# JetBot_Verteiler.net
KiCad netlist of a schematic drawn in EAGLE
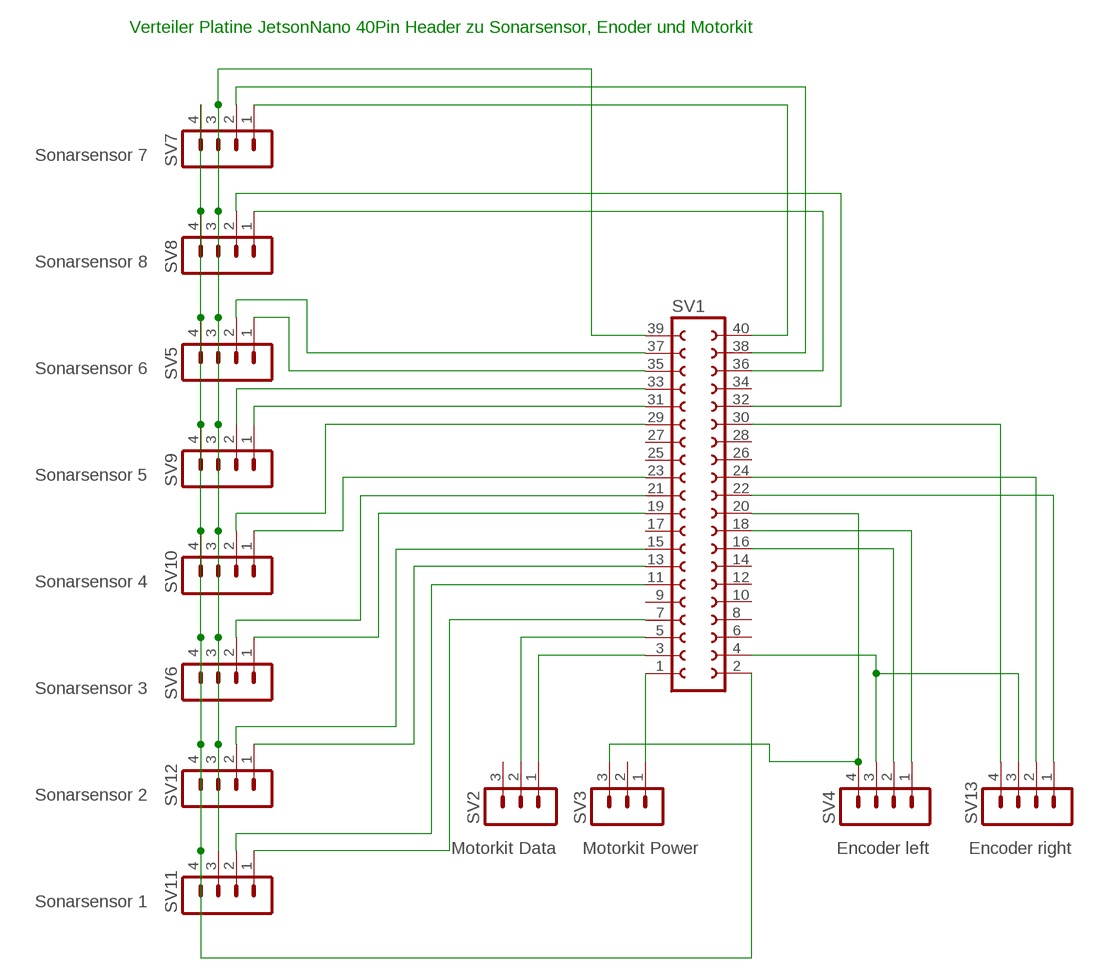
[diagram p0: schematic, sheet 1]

(export (version "E")
  (design (tool "Eeschema 10.0.6"))
  (components
    (comp (ref "SV1")
      (value "FE20-2")
      (footprint "eagle-import:FE20-2")
      (libsource (lib "eagle-import") (part "FE20-2"))
    )
    (comp (ref "SV2")
      (value "Motorkit Data")
      (footprint "eagle-import:MA03-1")
      (libsource (lib "eagle-import") (part "MA03-1"))
    )
    (comp (ref "SV3")
      (value "Motorkit Power")
      (footprint "eagle-import:MA03-1")
      (libsource (lib "eagle-import") (part "MA03-1"))
    )
    (comp (ref "SV4")
      (value "Encoder left")
      (footprint "eagle-import:MA04-1")
      (libsource (lib "eagle-import") (part "MA04-1"))
    )
    (comp (ref "SV5")
      (value "Sonarsensor 6")
      (footprint "eagle-import:MA04-1")
      (libsource (lib "eagle-import") (part "MA04-1"))
    )
    (comp (ref "SV6")
      (value "Sonarsensor 3")
      (footprint "eagle-import:MA04-1")
      (libsource (lib "eagle-import") (part "MA04-1"))
    )
    (comp (ref "SV7")
      (value "Sonarsensor 7")
      (footprint "eagle-import:MA04-1")
      (libsource (lib "eagle-import") (part "MA04-1"))
    )
    (comp (ref "SV8")
      (value "Sonarsensor 8")
      (footprint "eagle-import:MA04-1")
      (libsource (lib "eagle-import") (part "MA04-1"))
    )
    (comp (ref "SV9")
      (value "Sonarsensor 5")
      (footprint "eagle-import:MA04-1")
      (libsource (lib "eagle-import") (part "MA04-1"))
    )
    (comp (ref "SV10")
      (value "Sonarsensor 4")
      (footprint "eagle-import:MA04-1")
      (libsource (lib "eagle-import") (part "MA04-1"))
    )
    (comp (ref "SV11")
      (value "Sonarsensor 1")
      (footprint "eagle-import:MA04-1")
      (libsource (lib "eagle-import") (part "MA04-1"))
    )
    (comp (ref "SV12")
      (value "Sonarsensor 2")
      (footprint "eagle-import:MA04-1")
      (libsource (lib "eagle-import") (part "MA04-1"))
    )
    (comp (ref "SV13")
      (value "Encoder right")
      (footprint "eagle-import:MA04-1")
      (libsource (lib "eagle-import") (part "MA04-1"))
    )
  )
  (nets
    (net (code "1") (name "Net-(SV1-Pad1)") (class "Default")
      (node (ref "SV1") (pin "1") (pinfunction "1_1") (pintype "passive"))
      (node (ref "SV3") (pin "1") (pinfunction "1_1") (pintype "passive"))
    )
    (net (code "2") (name "Net-(SV1-Pad2)") (class "Default")
      (node (ref "SV1") (pin "2") (pinfunction "2_2") (pintype "passive"))
      (node (ref "SV10") (pin "4") (pinfunction "4_4") (pintype "passive"))
      (node (ref "SV11") (pin "4") (pinfunction "4_4") (pintype "passive"))
      (node (ref "SV12") (pin "4") (pinfunction "4_4") (pintype "passive"))
      (node (ref "SV5") (pin "4") (pinfunction "4_4") (pintype "passive"))
      (node (ref "SV6") (pin "4") (pinfunction "4_4") (pintype "passive"))
      (node (ref "SV7") (pin "4") (pinfunction "4_4") (pintype "passive"))
      (node (ref "SV8") (pin "4") (pinfunction "4_4") (pintype "passive"))
      (node (ref "SV9") (pin "4") (pinfunction "4_4") (pintype "passive"))
    )
    (net (code "3") (name "Net-(SV1-Pad3)") (class "Default")
      (node (ref "SV1") (pin "3") (pinfunction "3_3") (pintype "passive"))
      (node (ref "SV2") (pin "1") (pinfunction "1_1") (pintype "passive"))
    )
    (net (code "4") (name "Net-(SV1-Pad4)") (class "Default")
      (node (ref "SV1") (pin "4") (pinfunction "4_4") (pintype "passive"))
      (node (ref "SV13") (pin "3") (pinfunction "3_3") (pintype "passive"))
      (node (ref "SV4") (pin "3") (pinfunction "3_3") (pintype "passive"))
    )
    (net (code "5") (name "Net-(SV1-Pad5)") (class "Default")
      (node (ref "SV1") (pin "5") (pinfunction "5_5") (pintype "passive"))
      (node (ref "SV2") (pin "2") (pinfunction "2_2") (pintype "passive"))
    )
    (net (code "6") (name "Net-(SV1-Pad7)") (class "Default")
      (node (ref "SV1") (pin "7") (pinfunction "7_7") (pintype "passive"))
      (node (ref "SV11") (pin "1") (pinfunction "1_1") (pintype "passive"))
    )
    (net (code "7") (name "Net-(SV1-Pad11)") (class "Default")
      (node (ref "SV1") (pin "11") (pinfunction "11_11") (pintype "passive"))
      (node (ref "SV11") (pin "2") (pinfunction "2_2") (pintype "passive"))
    )
    (net (code "8") (name "Net-(SV1-Pad13)") (class "Default")
      (node (ref "SV1") (pin "13") (pinfunction "13_13") (pintype "passive"))
      (node (ref "SV12") (pin "1") (pinfunction "1_1") (pintype "passive"))
    )
    (net (code "9") (name "Net-(SV1-Pad15)") (class "Default")
      (node (ref "SV1") (pin "15") (pinfunction "15_15") (pintype "passive"))
      (node (ref "SV12") (pin "2") (pinfunction "2_2") (pintype "passive"))
    )
    (net (code "10") (name "Net-(SV1-Pad16)") (class "Default")
      (node (ref "SV1") (pin "16") (pinfunction "16_16") (pintype "passive"))
      (node (ref "SV4") (pin "2") (pinfunction "2_2") (pintype "passive"))
    )
    (net (code "11") (name "Net-(SV1-Pad18)") (class "Default")
      (node (ref "SV1") (pin "18") (pinfunction "18_18") (pintype "passive"))
      (node (ref "SV4") (pin "1") (pinfunction "1_1") (pintype "passive"))
    )
    (net (code "12") (name "Net-(SV1-Pad19)") (class "Default")
      (node (ref "SV1") (pin "19") (pinfunction "19_19") (pintype "passive"))
      (node (ref "SV6") (pin "1") (pinfunction "1_1") (pintype "passive"))
    )
    (net (code "13") (name "Net-(SV1-Pad20)") (class "Default")
      (node (ref "SV1") (pin "20") (pinfunction "20_20") (pintype "passive"))
      (node (ref "SV3") (pin "3") (pinfunction "3_3") (pintype "passive"))
      (node (ref "SV4") (pin "4") (pinfunction "4_4") (pintype "passive"))
    )
    (net (code "14") (name "Net-(SV1-Pad21)") (class "Default")
      (node (ref "SV1") (pin "21") (pinfunction "21_21") (pintype "passive"))
      (node (ref "SV6") (pin "2") (pinfunction "2_2") (pintype "passive"))
    )
    (net (code "15") (name "Net-(SV1-Pad22)") (class "Default")
      (node (ref "SV1") (pin "22") (pinfunction "22_22") (pintype "passive"))
      (node (ref "SV13") (pin "1") (pinfunction "1_1") (pintype "passive"))
    )
    (net (code "16") (name "Net-(SV1-Pad23)") (class "Default")
      (node (ref "SV1") (pin "23") (pinfunction "23_23") (pintype "passive"))
      (node (ref "SV10") (pin "1") (pinfunction "1_1") (pintype "passive"))
    )
    (net (code "17") (name "Net-(SV1-Pad24)") (class "Default")
      (node (ref "SV1") (pin "24") (pinfunction "24_24") (pintype "passive"))
      (node (ref "SV13") (pin "2") (pinfunction "2_2") (pintype "passive"))
    )
    (net (code "18") (name "Net-(SV1-Pad29)") (class "Default")
      (node (ref "SV1") (pin "29") (pinfunction "29_29") (pintype "passive"))
      (node (ref "SV10") (pin "2") (pinfunction "2_2") (pintype "passive"))
    )
    (net (code "19") (name "Net-(SV1-Pad30)") (class "Default")
      (node (ref "SV1") (pin "30") (pinfunction "30_30") (pintype "passive"))
      (node (ref "SV13") (pin "4") (pinfunction "4_4") (pintype "passive"))
    )
    (net (code "20") (name "Net-(SV1-Pad31)") (class "Default")
      (node (ref "SV1") (pin "31") (pinfunction "31_31") (pintype "passive"))
      (node (ref "SV9") (pin "1") (pinfunction "1_1") (pintype "passive"))
    )
    (net (code "21") (name "Net-(SV1-Pad32)") (class "Default")
      (node (ref "SV1") (pin "32") (pinfunction "32_32") (pintype "passive"))
      (node (ref "SV8") (pin "2") (pinfunction "2_2") (pintype "passive"))
    )
    (net (code "22") (name "Net-(SV1-Pad33)") (class "Default")
      (node (ref "SV1") (pin "33") (pinfunction "33_33") (pintype "passive"))
      (node (ref "SV9") (pin "2") (pinfunction "2_2") (pintype "passive"))
    )
    (net (code "23") (name "Net-(SV1-Pad35)") (class "Default")
      (node (ref "SV1") (pin "35") (pinfunction "35_35") (pintype "passive"))
      (node (ref "SV5") (pin "1") (pinfunction "1_1") (pintype "passive"))
    )
    (net (code "24") (name "Net-(SV1-Pad36)") (class "Default")
      (node (ref "SV1") (pin "36") (pinfunction "36_36") (pintype "passive"))
      (node (ref "SV8") (pin "1") (pinfunction "1_1") (pintype "passive"))
    )
    (net (code "25") (name "Net-(SV1-Pad37)") (class "Default")
      (node (ref "SV1") (pin "37") (pinfunction "37_37") (pintype "passive"))
      (node (ref "SV5") (pin "2") (pinfunction "2_2") (pintype "passive"))
    )
    (net (code "26") (name "Net-(SV1-Pad38)") (class "Default")
      (node (ref "SV1") (pin "38") (pinfunction "38_38") (pintype "passive"))
      (node (ref "SV7") (pin "2") (pinfunction "2_2") (pintype "passive"))
    )
    (net (code "27") (name "Net-(SV1-Pad39)") (class "Default")
      (node (ref "SV1") (pin "39") (pinfunction "39_39") (pintype "passive"))
      (node (ref "SV10") (pin "3") (pinfunction "3_3") (pintype "passive"))
      (node (ref "SV11") (pin "3") (pinfunction "3_3") (pintype "passive"))
      (node (ref "SV12") (pin "3") (pinfunction "3_3") (pintype "passive"))
      (node (ref "SV5") (pin "3") (pinfunction "3_3") (pintype "passive"))
      (node (ref "SV6") (pin "3") (pinfunction "3_3") (pintype "passive"))
      (node (ref "SV7") (pin "3") (pinfunction "3_3") (pintype "passive"))
      (node (ref "SV8") (pin "3") (pinfunction "3_3") (pintype "passive"))
      (node (ref "SV9") (pin "3") (pinfunction "3_3") (pintype "passive"))
    )
    (net (code "28") (name "Net-(SV1-Pad40)") (class "Default")
      (node (ref "SV1") (pin "40") (pinfunction "40_40") (pintype "passive"))
      (node (ref "SV7") (pin "1") (pinfunction "1_1") (pintype "passive"))
    )
    (net (code "29") (name "unconnected-(SV1-Pad6)") (class "Default")
      (node (ref "SV1") (pin "6") (pinfunction "6_6") (pintype "passive"))
    )
    (net (code "30") (name "unconnected-(SV1-Pad8)") (class "Default")
      (node (ref "SV1") (pin "8") (pinfunction "8_8") (pintype "passive"))
    )
    (net (code "31") (name "unconnected-(SV1-Pad9)") (class "Default")
      (node (ref "SV1") (pin "9") (pinfunction "9_9") (pintype "passive"))
    )
    (net (code "32") (name "unconnected-(SV1-Pad10)") (class "Default")
      (node (ref "SV1") (pin "10") (pinfunction "10_10") (pintype "passive"))
    )
    (net (code "33") (name "unconnected-(SV1-Pad12)") (class "Default")
      (node (ref "SV1") (pin "12") (pinfunction "12_12") (pintype "passive"))
    )
    (net (code "34") (name "unconnected-(SV1-Pad14)") (class "Default")
      (node (ref "SV1") (pin "14") (pinfunction "14_14") (pintype "passive"))
    )
    (net (code "35") (name "unconnected-(SV1-Pad17)") (class "Default")
      (node (ref "SV1") (pin "17") (pinfunction "17_17") (pintype "passive"))
    )
    (net (code "36") (name "unconnected-(SV1-Pad25)") (class "Default")
      (node (ref "SV1") (pin "25") (pinfunction "25_25") (pintype "passive"))
    )
    (net (code "37") (name "unconnected-(SV1-Pad26)") (class "Default")
      (node (ref "SV1") (pin "26") (pinfunction "26_26") (pintype "passive"))
    )
    (net (code "38") (name "unconnected-(SV1-Pad27)") (class "Default")
      (node (ref "SV1") (pin "27") (pinfunction "27_27") (pintype "passive"))
    )
    (net (code "39") (name "unconnected-(SV1-Pad28)") (class "Default")
      (node (ref "SV1") (pin "28") (pinfunction "28_28") (pintype "passive"))
    )
    (net (code "40") (name "unconnected-(SV1-Pad34)") (class "Default")
      (node (ref "SV1") (pin "34") (pinfunction "34_34") (pintype "passive"))
    )
    (net (code "41") (name "unconnected-(SV2-Pad3)") (class "Default")
      (node (ref "SV2") (pin "3") (pinfunction "3_3") (pintype "passive"))
    )
    (net (code "42") (name "unconnected-(SV3-Pad2)") (class "Default")
      (node (ref "SV3") (pin "2") (pinfunction "2_2") (pintype "passive"))
    )
  )
)
